# ProProject_Xtal_LO_Ver0_1_2023-07-24.net
KiCad netlist of a schematic drawn in EasyEDA Pro
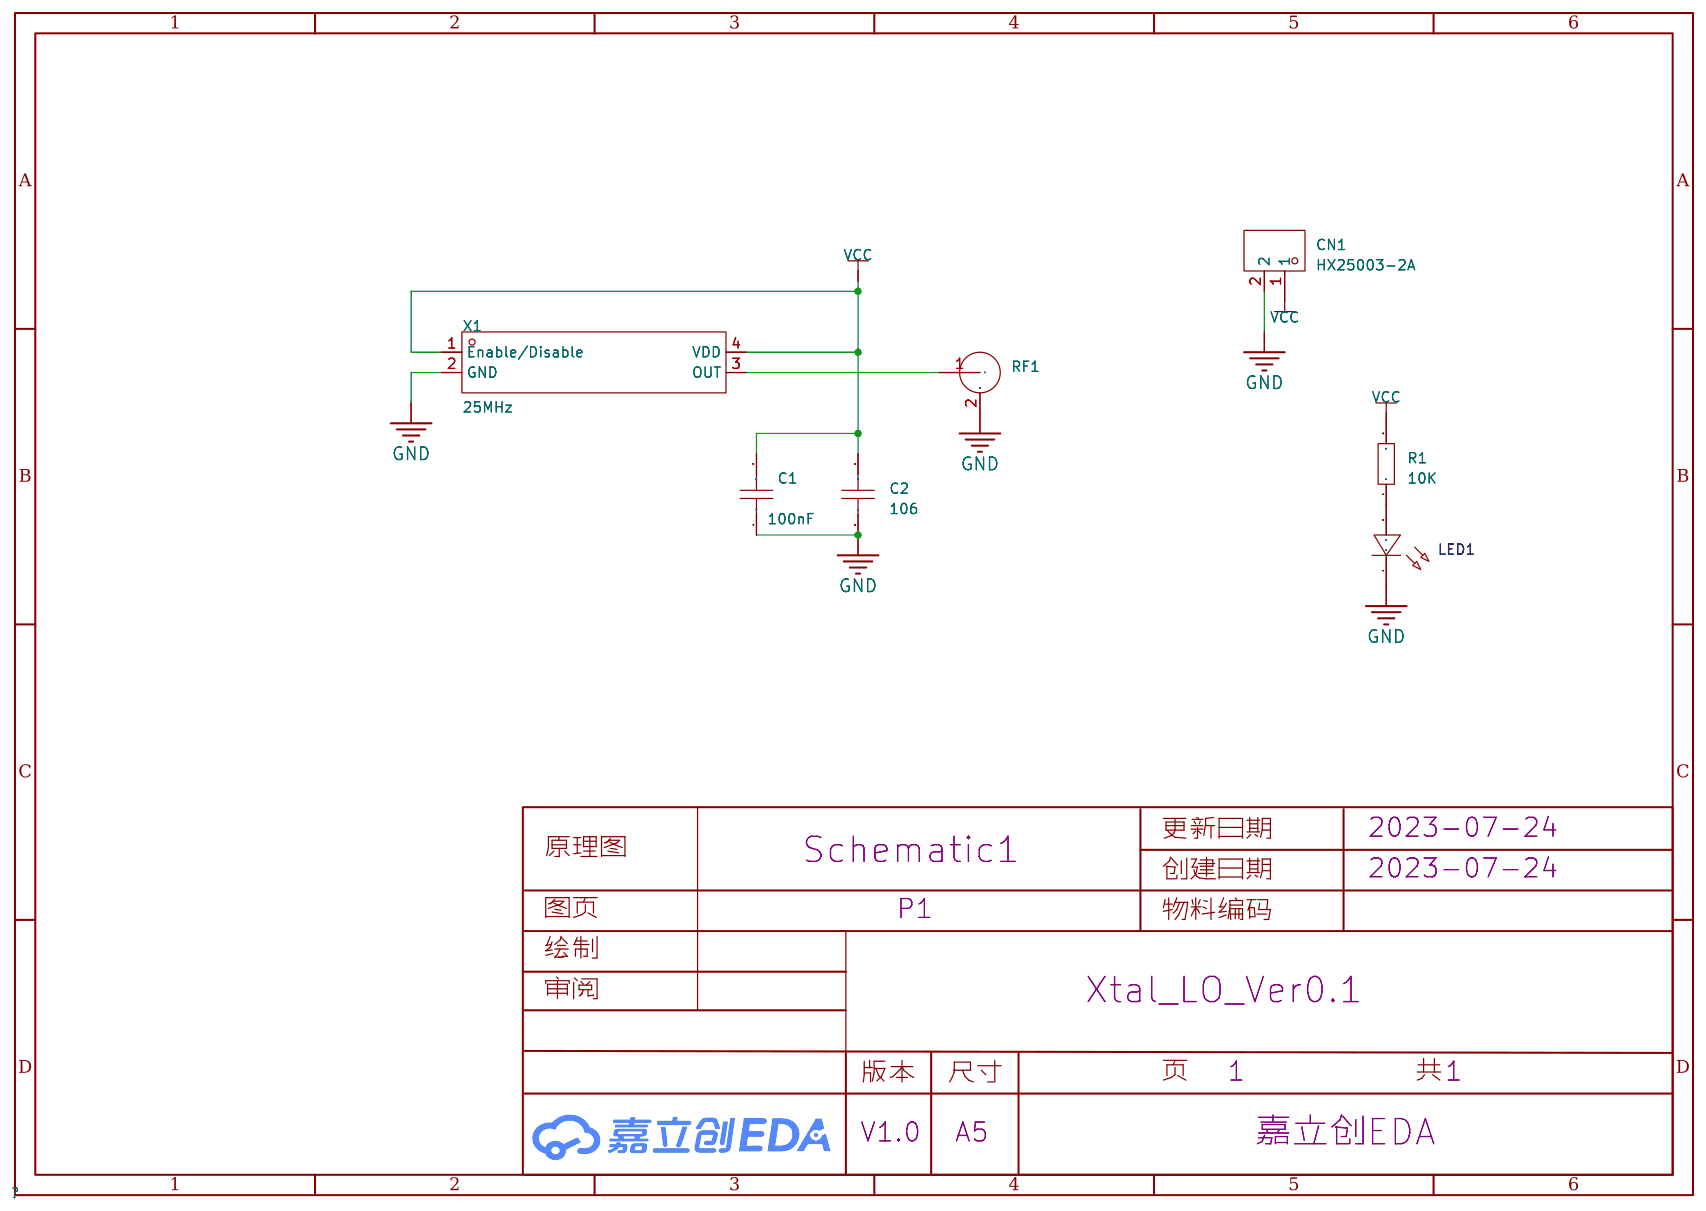
[diagram p0: schematic sheet]

(export (version "E")
  (design (tool "Eeschema 10.0.6"))
  (components
    (comp (ref "C1")
      (value "100nF")
      (footprint "easyedapro:C1206")
      (libsource (lib "easyedapro") (part "CapAcitance"))
    )
    (comp (ref "C2")
      (value "106")
      (footprint "easyedapro:C1206")
      (libsource (lib "easyedapro") (part "CapAcitance"))
    )
    (comp (ref "CN1")
      (value "HX25003-2A")
      (footprint "easyedapro:CONN-TH_2P-P2.50_HX25003-2A")
      (description "参考系列:XH;间距:2.5mm;插针结构:1x2P;排数:1;每排PIN数:2;行距:-;公母:公型插针;安装方式:直插;额定电流:-;工作温度范围:-;")
      (fields (field (name "Manufacturer") "HX(红星)"))
      (libsource (lib "easyedapro") (part "HX25003-2A"))
    )
    (comp (ref "LED1")
      (value "~")
      (footprint "easyedapro:LED_0805")
      (libsource (lib "easyedapro") (part "LED_G"))
    )
    (comp (ref "R1") (value "10K") (footprint "easyedapro:R0603") (libsource (lib "easyedapro") (part "电阻")))
    (comp (ref "RF1")
      (value "{ManufacturerPart!}")
      (footprint "easyedapro:SMA-SMD_BWSMA-KE-P001")
      (description "连接器类型:板端;射频系列:SMA;接口类型:内孔;端口数量:1;阻抗:-;频率-最大值:-;样式:偏脚;接口直径:5.2mm;接口长度/高度:-;工作温度范围:-;")
      (fields
        (field (name "Manufacturer Part") "BWSMA-KE-P001")
        (field (name "Manufacturer") "BATWIRELESS(蝙蝠无线)")
      )
      (libsource (lib "easyedapro") (part "SMA"))
    )
    (comp (ref "X1")
      (value "25MHz")
      (footprint "easyedapro:OSC-SMD_4P-L3.2-W2.5-BL")
      (description "频率:25MHz;频率稳定度:±10ppm;工作电压:1.8V~3.3V;")
      (fields (field (name "Manufacturer Part") "OT322525MJBA4SL") (field (name "Manufacturer") "YXC(扬兴晶振)"))
      (libsource (lib "easyedapro") (part "OT322525MJBA4SL"))
    )
  )
  (nets
    (net (code "1") (name "GND") (class "Default")
      (node (ref "C1") (pin "1") (pinfunction "1_1") (pintype "input"))
      (node (ref "C2") (pin "1") (pinfunction "1_1") (pintype "input"))
      (node (ref "CN1") (pin "2") (pinfunction "2_2") (pintype "input"))
      (node (ref "LED1") (pin "1") (pinfunction "C_1") (pintype "input"))
      (node (ref "RF1") (pin "2") (pinfunction "2_2") (pintype "input"))
      (node (ref "X1") (pin "2") (pinfunction "GND_2") (pintype "input"))
    )
    (net (code "2") (name "Net-(LED1-A)") (class "Default")
      (node (ref "LED1") (pin "2") (pinfunction "A_2") (pintype "input"))
      (node (ref "R1") (pin "1") (pinfunction "1_1") (pintype "input"))
    )
    (net (code "3") (name "Net-(X1-OUT)") (class "Default")
      (node (ref "RF1") (pin "1") (pinfunction "1_1") (pintype "input"))
      (node (ref "X1") (pin "3") (pinfunction "OUT_3") (pintype "input"))
    )
    (net (code "4") (name "VCC") (class "Default")
      (node (ref "C1") (pin "2") (pinfunction "2_2") (pintype "input"))
      (node (ref "C2") (pin "2") (pinfunction "2_2") (pintype "input"))
      (node (ref "CN1") (pin "1") (pinfunction "1_1") (pintype "input"))
      (node (ref "R1") (pin "2") (pinfunction "2_2") (pintype "input"))
      (node (ref "X1") (pin "1") (pinfunction "Enable/Disable_1") (pintype "input"))
      (node (ref "X1") (pin "4") (pinfunction "VDD_4") (pintype "input"))
    )
  )
)
